# board.net
KiCad netlist of a schematic drawn in EAGLE
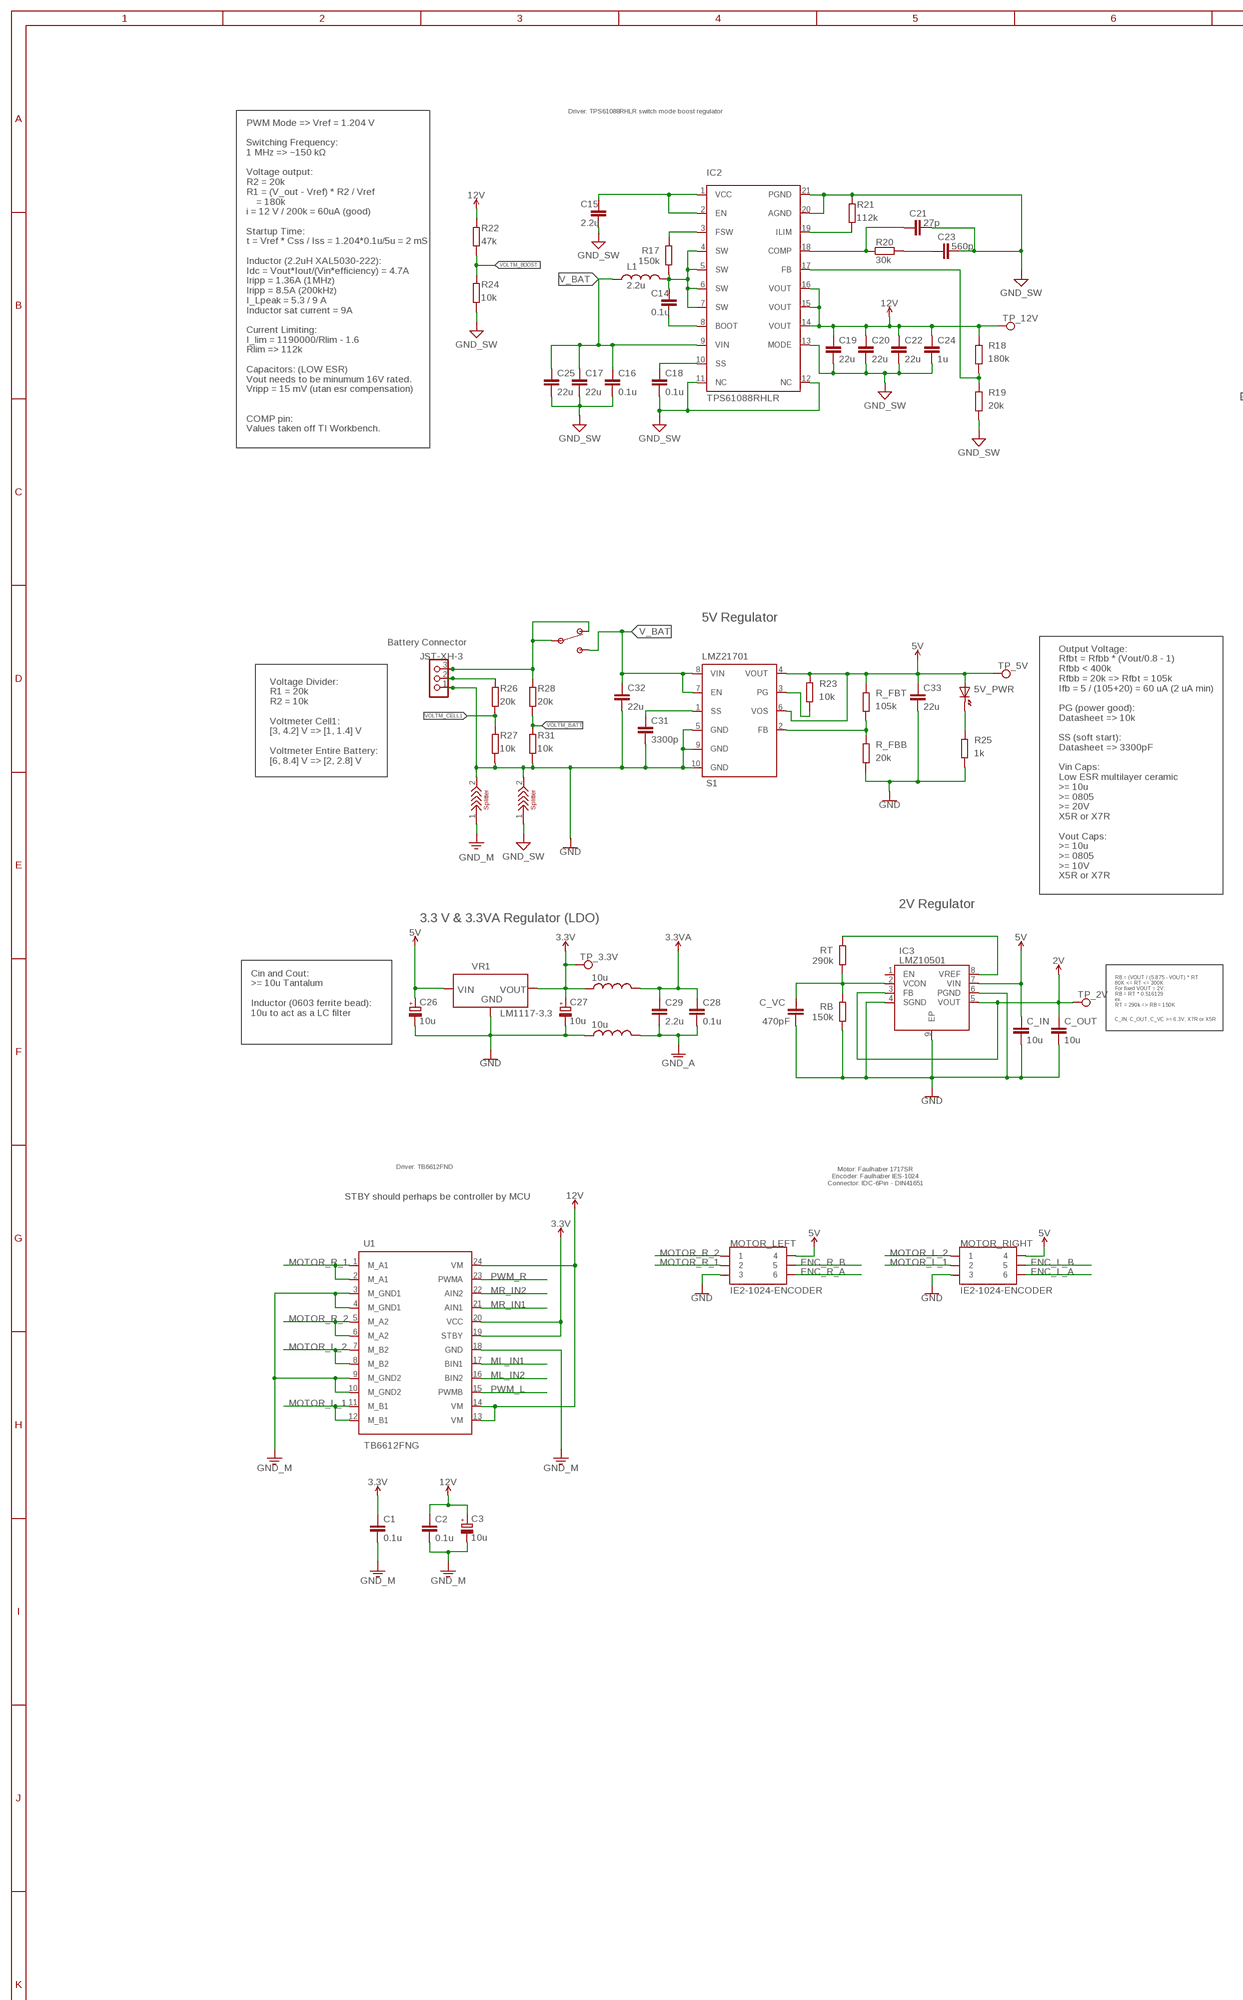
[diagram p0: schematic, sheet 1, part 1 of 3]
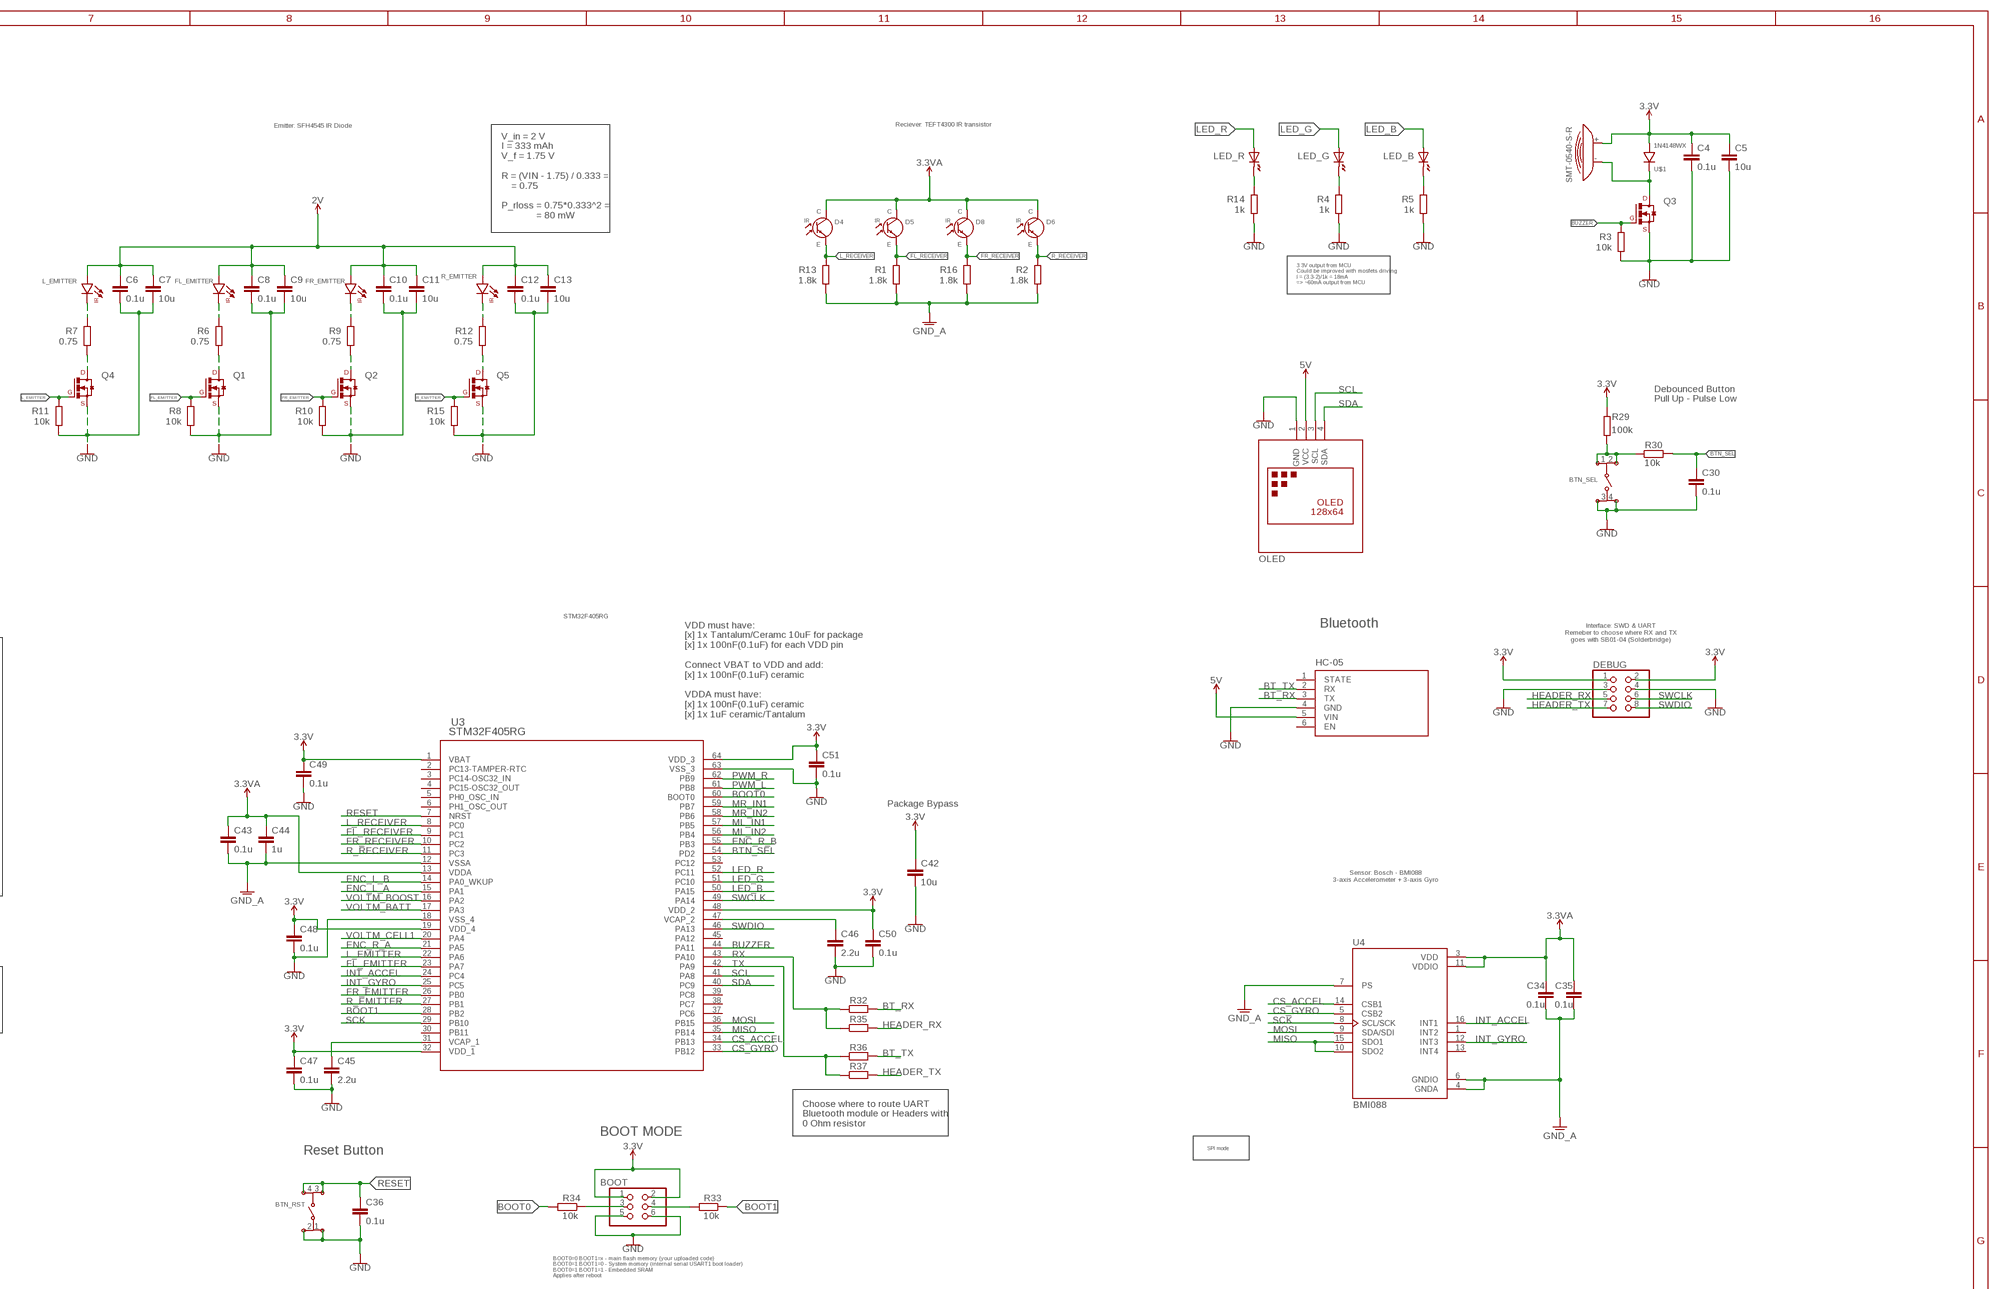
[diagram p1: schematic, sheet 1, part 2 of 3]
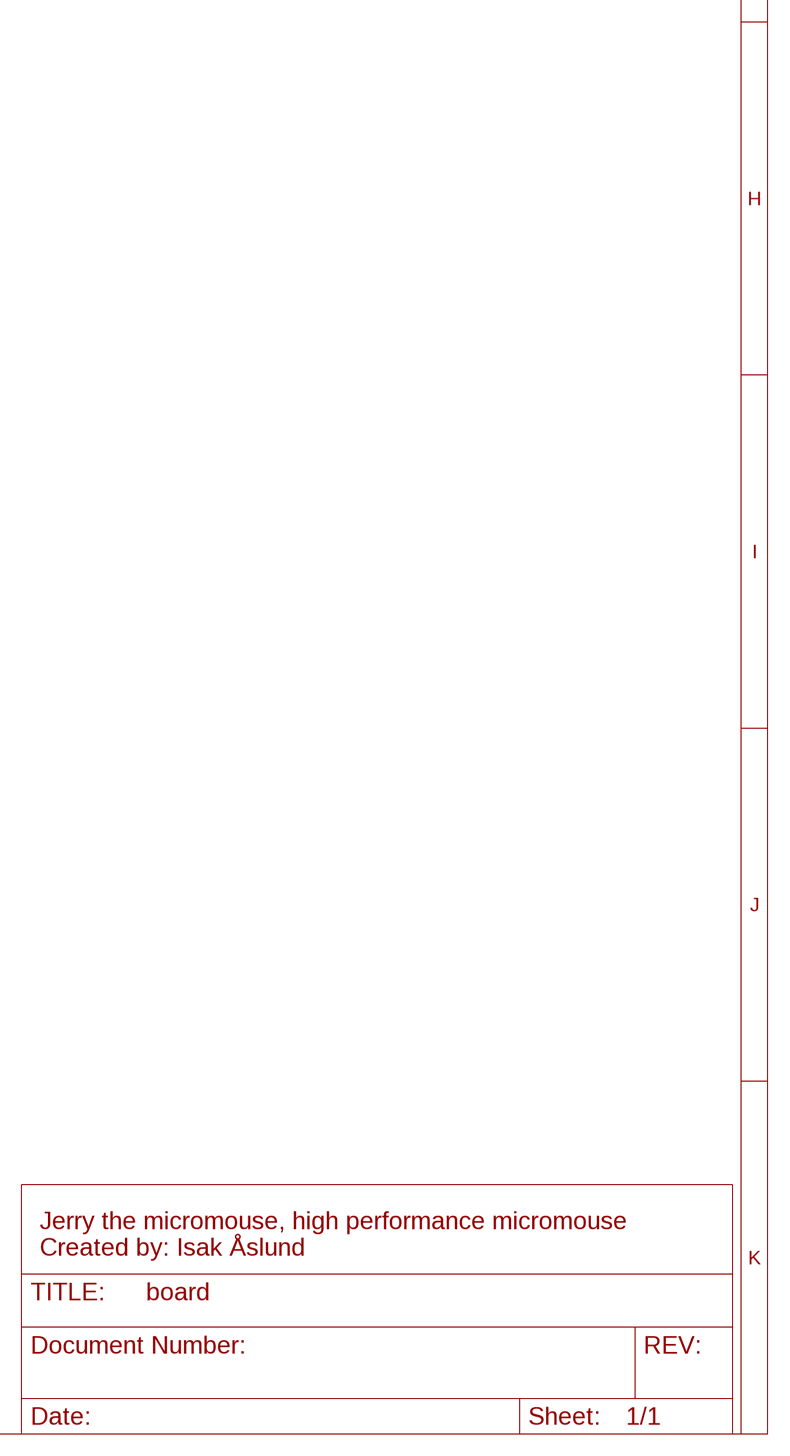
[diagram p2: schematic, sheet 1, part 3 of 3]

(export (version "E")
  (design (tool "Eeschema 10.0.6"))
  (components
    (comp (ref "5V_PWR")
      (value "CHIP-LED0603")
      (footprint "eagle-import:CHIP-LED0603")
      (libsource (lib "eagle-import") (part "CHIP-LED0603"))
    )
    (comp (ref "BOOT")
      (value "PINHD-2X3")
      (footprint "eagle-import:2X03")
      (libsource (lib "eagle-import") (part "PINHD-2X3"))
    )
    (comp (ref "BTN_RST")
      (value "KMR621NGLFS")
      (footprint "eagle-import:KMR621NGLFS")
      (libsource (lib "eagle-import") (part "KMR621NGLFS"))
    )
    (comp (ref "BTN_SEL")
      (value "KMR621NGLFS")
      (footprint "eagle-import:KMR621NGLFS")
      (libsource (lib "eagle-import") (part "KMR621NGLFS"))
    )
    (comp (ref "C1")
      (value "0.1u")
      (footprint "eagle-import:C0603")
      (libsource (lib "eagle-import") (part "C0603"))
    )
    (comp (ref "C2")
      (value "0.1u")
      (footprint "eagle-import:C0603")
      (libsource (lib "eagle-import") (part "C0603"))
    )
    (comp (ref "C3")
      (value "10u")
      (footprint "eagle-import:EIA_6032-28")
      (libsource (lib "eagle-import") (part "KEMET_C"))
    )
    (comp (ref "C4")
      (value "0.1u")
      (footprint "eagle-import:C0603")
      (libsource (lib "eagle-import") (part "C0603"))
    )
    (comp (ref "C5")
      (value "10u")
      (footprint "eagle-import:C0603")
      (libsource (lib "eagle-import") (part "C0603"))
    )
    (comp (ref "C6")
      (value "0.1u")
      (footprint "eagle-import:C0603")
      (libsource (lib "eagle-import") (part "C0603"))
    )
    (comp (ref "C7")
      (value "10u")
      (footprint "eagle-import:C0603")
      (libsource (lib "eagle-import") (part "C0603"))
    )
    (comp (ref "C8")
      (value "0.1u")
      (footprint "eagle-import:C0603")
      (libsource (lib "eagle-import") (part "C0603"))
    )
    (comp (ref "C9")
      (value "10u")
      (footprint "eagle-import:C0603")
      (libsource (lib "eagle-import") (part "C0603"))
    )
    (comp (ref "C10")
      (value "0.1u")
      (footprint "eagle-import:C0603")
      (libsource (lib "eagle-import") (part "C0603"))
    )
    (comp (ref "C11")
      (value "10u")
      (footprint "eagle-import:C0603")
      (libsource (lib "eagle-import") (part "C0603"))
    )
    (comp (ref "C12")
      (value "0.1u")
      (footprint "eagle-import:C0603")
      (libsource (lib "eagle-import") (part "C0603"))
    )
    (comp (ref "C13")
      (value "10u")
      (footprint "eagle-import:C0603")
      (libsource (lib "eagle-import") (part "C0603"))
    )
    (comp (ref "C14")
      (value "0.1u")
      (footprint "eagle-import:C0603")
      (libsource (lib "eagle-import") (part "C0603"))
    )
    (comp (ref "C15")
      (value "2.2u")
      (footprint "eagle-import:C0603")
      (libsource (lib "eagle-import") (part "C0603"))
    )
    (comp (ref "C16")
      (value "0.1u")
      (footprint "eagle-import:C0805")
      (libsource (lib "eagle-import") (part "C0805"))
    )
    (comp (ref "C17")
      (value "22u")
      (footprint "eagle-import:C0805")
      (libsource (lib "eagle-import") (part "C0805"))
    )
    (comp (ref "C18")
      (value "0.1u")
      (footprint "eagle-import:C0603")
      (libsource (lib "eagle-import") (part "C0603"))
    )
    (comp (ref "C19")
      (value "22u")
      (footprint "eagle-import:C0805")
      (libsource (lib "eagle-import") (part "C0805"))
    )
    (comp (ref "C20")
      (value "22u")
      (footprint "eagle-import:C0805")
      (libsource (lib "eagle-import") (part "C0805"))
    )
    (comp (ref "C21")
      (value "27p")
      (footprint "eagle-import:C0603")
      (libsource (lib "eagle-import") (part "C0603"))
    )
    (comp (ref "C22")
      (value "22u")
      (footprint "eagle-import:C0805")
      (libsource (lib "eagle-import") (part "C0805"))
    )
    (comp (ref "C23")
      (value "560p")
      (footprint "eagle-import:C0603")
      (libsource (lib "eagle-import") (part "C0603"))
    )
    (comp (ref "C24")
      (value "1u")
      (footprint "eagle-import:C0805")
      (libsource (lib "eagle-import") (part "C0805"))
    )
    (comp (ref "C25")
      (value "22u")
      (footprint "eagle-import:C0805")
      (libsource (lib "eagle-import") (part "C0805"))
    )
    (comp (ref "C26")
      (value "10u")
      (footprint "eagle-import:SMC_A")
      (libsource (lib "eagle-import") (part "SMC_A"))
    )
    (comp (ref "C27")
      (value "10u")
      (footprint "eagle-import:SMC_A")
      (libsource (lib "eagle-import") (part "SMC_A"))
    )
    (comp (ref "C28")
      (value "0.1u")
      (footprint "eagle-import:C0603")
      (libsource (lib "eagle-import") (part "C0603"))
    )
    (comp (ref "C29")
      (value "2.2u")
      (footprint "eagle-import:C0603")
      (libsource (lib "eagle-import") (part "C0603"))
    )
    (comp (ref "C30")
      (value "0.1u")
      (footprint "eagle-import:C0603")
      (libsource (lib "eagle-import") (part "C0603"))
    )
    (comp (ref "C31")
      (value "3300p")
      (footprint "eagle-import:C0603")
      (libsource (lib "eagle-import") (part "C0603"))
    )
    (comp (ref "C32")
      (value "22u")
      (footprint "eagle-import:C0805")
      (libsource (lib "eagle-import") (part "C0805"))
    )
    (comp (ref "C33")
      (value "22u")
      (footprint "eagle-import:C0805")
      (libsource (lib "eagle-import") (part "C0805"))
    )
    (comp (ref "C34")
      (value "0.1u")
      (footprint "eagle-import:C0603")
      (libsource (lib "eagle-import") (part "C0603"))
    )
    (comp (ref "C35")
      (value "0.1u")
      (footprint "eagle-import:C0603")
      (libsource (lib "eagle-import") (part "C0603"))
    )
    (comp (ref "C36")
      (value "0.1u")
      (footprint "eagle-import:C0603")
      (libsource (lib "eagle-import") (part "C0603"))
    )
    (comp (ref "C42")
      (value "10u")
      (footprint "eagle-import:C0603")
      (libsource (lib "eagle-import") (part "C0603"))
    )
    (comp (ref "C43")
      (value "0.1u")
      (footprint "eagle-import:C0603")
      (libsource (lib "eagle-import") (part "C0603"))
    )
    (comp (ref "C44")
      (value "1u")
      (footprint "eagle-import:C0603")
      (libsource (lib "eagle-import") (part "C0603"))
    )
    (comp (ref "C45")
      (value "2.2u")
      (footprint "eagle-import:C0603")
      (libsource (lib "eagle-import") (part "C0603"))
    )
    (comp (ref "C46")
      (value "2.2u")
      (footprint "eagle-import:C0603")
      (libsource (lib "eagle-import") (part "C0603"))
    )
    (comp (ref "C47")
      (value "0.1u")
      (footprint "eagle-import:C0603")
      (libsource (lib "eagle-import") (part "C0603"))
    )
    (comp (ref "C48")
      (value "0.1u")
      (footprint "eagle-import:C0603")
      (libsource (lib "eagle-import") (part "C0603"))
    )
    (comp (ref "C49")
      (value "0.1u")
      (footprint "eagle-import:C0603")
      (libsource (lib "eagle-import") (part "C0603"))
    )
    (comp (ref "C50")
      (value "0.1u")
      (footprint "eagle-import:C0603")
      (libsource (lib "eagle-import") (part "C0603"))
    )
    (comp (ref "C51")
      (value "0.1u")
      (footprint "eagle-import:C0603")
      (libsource (lib "eagle-import") (part "C0603"))
    )
    (comp (ref "C_IN")
      (value "10u")
      (footprint "eagle-import:C0805")
      (libsource (lib "eagle-import") (part "C0805"))
    )
    (comp (ref "C_OUT")
      (value "10u")
      (footprint "eagle-import:C0805")
      (libsource (lib "eagle-import") (part "C0805"))
    )
    (comp (ref "C_VC")
      (value "470pF")
      (footprint "eagle-import:C0603")
      (libsource (lib "eagle-import") (part "C0603"))
    )
    (comp (ref "D4")
      (value "TEFT4300")
      (footprint "eagle-import:3MM_PHOTOTRANSISTOR")
      (libsource (lib "eagle-import") (part "TEFT4300"))
    )
    (comp (ref "D5")
      (value "TEFT4300")
      (footprint "eagle-import:3MM_PHOTOTRANSISTOR")
      (libsource (lib "eagle-import") (part "TEFT4300"))
    )
    (comp (ref "D6")
      (value "TEFT4300")
      (footprint "eagle-import:3MM_PHOTOTRANSISTOR")
      (libsource (lib "eagle-import") (part "TEFT4300"))
    )
    (comp (ref "D8")
      (value "TEFT4300")
      (footprint "eagle-import:3MM_PHOTOTRANSISTOR")
      (libsource (lib "eagle-import") (part "TEFT4300"))
    )
    (comp (ref "DEBUG")
      (value "PINHD-2X4")
      (footprint "eagle-import:2X04")
      (libsource (lib "eagle-import") (part "PINHD-2X4"))
    )
    (comp (ref "FL_EMITTER")
      (value "SFH_4545")
      (footprint "eagle-import:SFH_4545")
      (libsource (lib "eagle-import") (part "SFH_4545"))
    )
    (comp (ref "FP1")
      (value "10u")
      (footprint "eagle-import:R0805")
      (libsource (lib "eagle-import") (part "WE-CBF_0805"))
    )
    (comp (ref "FP2")
      (value "10u")
      (footprint "eagle-import:R0805")
      (libsource (lib "eagle-import") (part "WE-CBF_0805"))
    )
    (comp (ref "FR_EMITTER")
      (value "SFH_4545")
      (footprint "eagle-import:SFH_4545")
      (libsource (lib "eagle-import") (part "SFH_4545"))
    )
    (comp (ref "HC-05")
      (value "WIRELESS-BLUETOOTH-HC-05")
      (footprint "eagle-import:WIRELESS-BLUETOOTH-HC-05")
      (libsource (lib "eagle-import") (part "WIRELESS-BLUETOOTH-HC-05"))
    )
    (comp (ref "IC2")
      (value "TPS61088RHLR")
      (footprint "eagle-import:RHL(R-PVQFN-N20)_1")
      (fields (field (name "MOUSER_PART_NUMBER") "595-TPS61088RHLR"))
      (libsource (lib "eagle-import") (part "TPS61088RHLR"))
    )
    (comp (ref "IC3")
      (value "LMZ10501")
      (footprint "eagle-import:SON65P260X300X150-9N")
      (fields
        (field (name "MANUFACTURER_PART_NUMBER") "LMZ10501SILT")
        (field (name "MOUSER_PART_NUMBER") "595-LMZ10501SILT")
      )
      (libsource (lib "eagle-import") (part "LMZ10501"))
    )
    (comp (ref "L1")
      (value "2.2u")
      (footprint "eagle-import:XAL5030")
      (fields
        (field (name "MANUFACTURER_PART_NUMBER") "XAL5030-222MEC")
        (field (name "MOUSER_PART_NUMBER") "994-XAL5030-222MEC")
      )
      (libsource (lib "eagle-import") (part "XAL5030-222MEC"))
    )
    (comp (ref "LED_B")
      (value "CHIP-LED0603")
      (footprint "eagle-import:CHIP-LED0603")
      (libsource (lib "eagle-import") (part "CHIP-LED0603"))
    )
    (comp (ref "LED_G")
      (value "CHIP-LED0603")
      (footprint "eagle-import:CHIP-LED0603")
      (libsource (lib "eagle-import") (part "CHIP-LED0603"))
    )
    (comp (ref "LED_R")
      (value "CHIP-LED0603")
      (footprint "eagle-import:CHIP-LED0603")
      (libsource (lib "eagle-import") (part "CHIP-LED0603"))
    )
    (comp (ref "L_EMITTER")
      (value "SFH_4545")
      (footprint "eagle-import:SFH_4545")
      (libsource (lib "eagle-import") (part "SFH_4545"))
    )
    (comp (ref "MOTOR_LEFT")
      (value "IE2-1024-ENCODER")
      (footprint "eagle-import:IE2-1024-ENCODER")
      (libsource (lib "eagle-import") (part "IE2-1024-ENCODER"))
    )
    (comp (ref "MOTOR_RIGHT")
      (value "IE2-1024-ENCODER")
      (footprint "eagle-import:IE2-1024-ENCODER")
      (libsource (lib "eagle-import") (part "IE2-1024-ENCODER"))
    )
    (comp (ref "OLED")
      (value "DISPLAY-OLED-128X64-I2C")
      (footprint "eagle-import:DISPLAY-OLED-128X64-I2C")
      (libsource (lib "eagle-import") (part "DISPLAY-OLED-128X64-I2C"))
    )
    (comp (ref "Q1")
      (value "IRFML8244TRPBF")
      (footprint "eagle-import:SOT95P235X110-3")
      (libsource (lib "eagle-import") (part "IRFML8244TRPBF"))
    )
    (comp (ref "Q2")
      (value "IRFML8244TRPBF")
      (footprint "eagle-import:SOT95P235X110-3")
      (libsource (lib "eagle-import") (part "IRFML8244TRPBF"))
    )
    (comp (ref "Q3")
      (value "IRFML8244TRPBF")
      (footprint "eagle-import:SOT95P235X110-3")
      (libsource (lib "eagle-import") (part "IRFML8244TRPBF"))
    )
    (comp (ref "Q4")
      (value "IRFML8244TRPBF")
      (footprint "eagle-import:SOT95P235X110-3")
      (libsource (lib "eagle-import") (part "IRFML8244TRPBF"))
    )
    (comp (ref "Q5")
      (value "IRFML8244TRPBF")
      (footprint "eagle-import:SOT95P235X110-3")
      (libsource (lib "eagle-import") (part "IRFML8244TRPBF"))
    )
    (comp (ref "R1")
      (value "1.8k")
      (footprint "eagle-import:R0603")
      (libsource (lib "eagle-import") (part "R0603"))
    )
    (comp (ref "R2")
      (value "1.8k")
      (footprint "eagle-import:R0603")
      (libsource (lib "eagle-import") (part "R0603"))
    )
    (comp (ref "R3")
      (value "10k")
      (footprint "eagle-import:R0603")
      (libsource (lib "eagle-import") (part "R0603"))
    )
    (comp (ref "R4")
      (value "1k")
      (footprint "eagle-import:R0603")
      (libsource (lib "eagle-import") (part "R0603"))
    )
    (comp (ref "R5")
      (value "1k")
      (footprint "eagle-import:R0603")
      (libsource (lib "eagle-import") (part "R0603"))
    )
    (comp (ref "R6")
      (value "0.75")
      (footprint "eagle-import:R0603")
      (libsource (lib "eagle-import") (part "R0603"))
    )
    (comp (ref "R7")
      (value "0.75")
      (footprint "eagle-import:R0603")
      (libsource (lib "eagle-import") (part "R0603"))
    )
    (comp (ref "R8")
      (value "10k")
      (footprint "eagle-import:R0603")
      (libsource (lib "eagle-import") (part "R0603"))
    )
    (comp (ref "R9")
      (value "0.75")
      (footprint "eagle-import:R0603")
      (libsource (lib "eagle-import") (part "R0603"))
    )
    (comp (ref "R10")
      (value "10k")
      (footprint "eagle-import:R0603")
      (libsource (lib "eagle-import") (part "R0603"))
    )
    (comp (ref "R11")
      (value "10k")
      (footprint "eagle-import:R0603")
      (libsource (lib "eagle-import") (part "R0603"))
    )
    (comp (ref "R12")
      (value "0.75")
      (footprint "eagle-import:R0603")
      (libsource (lib "eagle-import") (part "R0603"))
    )
    (comp (ref "R13")
      (value "1.8k")
      (footprint "eagle-import:R0603")
      (libsource (lib "eagle-import") (part "R0603"))
    )
    (comp (ref "R14")
      (value "1k")
      (footprint "eagle-import:R0603")
      (libsource (lib "eagle-import") (part "R0603"))
    )
    (comp (ref "R15")
      (value "10k")
      (footprint "eagle-import:R0603")
      (libsource (lib "eagle-import") (part "R0603"))
    )
    (comp (ref "R16")
      (value "1.8k")
      (footprint "eagle-import:R0603")
      (libsource (lib "eagle-import") (part "R0603"))
    )
    (comp (ref "R17")
      (value "150k")
      (footprint "eagle-import:R0603")
      (libsource (lib "eagle-import") (part "R0603"))
    )
    (comp (ref "R18")
      (value "180k")
      (footprint "eagle-import:R0603")
      (libsource (lib "eagle-import") (part "R0603"))
    )
    (comp (ref "R19")
      (value "20k")
      (footprint "eagle-import:R0603")
      (libsource (lib "eagle-import") (part "R0603"))
    )
    (comp (ref "R20")
      (value "30k")
      (footprint "eagle-import:R0603")
      (libsource (lib "eagle-import") (part "R0603"))
    )
    (comp (ref "R21")
      (value "112k")
      (footprint "eagle-import:R0603")
      (libsource (lib "eagle-import") (part "R0603"))
    )
    (comp (ref "R22")
      (value "47k")
      (footprint "eagle-import:R0603")
      (libsource (lib "eagle-import") (part "R0603"))
    )
    (comp (ref "R23")
      (value "10k")
      (footprint "eagle-import:R0603")
      (fields (field (name "TOLERANCE") "1%"))
      (libsource (lib "eagle-import") (part "R0603"))
    )
    (comp (ref "R24")
      (value "10k")
      (footprint "eagle-import:R0603")
      (libsource (lib "eagle-import") (part "R0603"))
    )
    (comp (ref "R25")
      (value "1k")
      (footprint "eagle-import:R0603")
      (libsource (lib "eagle-import") (part "R0603"))
    )
    (comp (ref "R26")
      (value "20k")
      (footprint "eagle-import:R0603")
      (libsource (lib "eagle-import") (part "R0603"))
    )
    (comp (ref "R27")
      (value "10k")
      (footprint "eagle-import:R0603")
      (libsource (lib "eagle-import") (part "R0603"))
    )
    (comp (ref "R28")
      (value "20k")
      (footprint "eagle-import:R0603")
      (libsource (lib "eagle-import") (part "R0603"))
    )
    (comp (ref "R29")
      (value "100k")
      (footprint "eagle-import:R0603")
      (libsource (lib "eagle-import") (part "R0603"))
    )
    (comp (ref "R30")
      (value "10k")
      (footprint "eagle-import:R0603")
      (libsource (lib "eagle-import") (part "R0603"))
    )
    (comp (ref "R31")
      (value "10k")
      (footprint "eagle-import:R0603")
      (libsource (lib "eagle-import") (part "R0603"))
    )
    (comp (ref "R32")
      (value "0")
      (footprint "eagle-import:R0603")
      (libsource (lib "eagle-import") (part "R0603"))
    )
    (comp (ref "R33")
      (value "10k")
      (footprint "eagle-import:R0603")
      (libsource (lib "eagle-import") (part "R0603"))
    )
    (comp (ref "R34")
      (value "10k")
      (footprint "eagle-import:R0603")
      (libsource (lib "eagle-import") (part "R0603"))
    )
    (comp (ref "R35")
      (value "0")
      (footprint "eagle-import:R0603")
      (libsource (lib "eagle-import") (part "R0603"))
    )
    (comp (ref "R36")
      (value "0")
      (footprint "eagle-import:R0603")
      (libsource (lib "eagle-import") (part "R0603"))
    )
    (comp (ref "R37")
      (value "0")
      (footprint "eagle-import:R0603")
      (libsource (lib "eagle-import") (part "R0603"))
    )
    (comp (ref "RB")
      (value "150k")
      (footprint "eagle-import:R0603")
      (libsource (lib "eagle-import") (part "R0603"))
    )
    (comp (ref "RT")
      (value "290k")
      (footprint "eagle-import:R0603")
      (fields (field (name "TOLERANCE") "1%"))
      (libsource (lib "eagle-import") (part "R0603"))
    )
    (comp (ref "R_EMITTER")
      (value "SFH_4545")
      (footprint "eagle-import:SFH_4545")
      (libsource (lib "eagle-import") (part "SFH_4545"))
    )
    (comp (ref "R_FBB")
      (value "20k")
      (footprint "eagle-import:R0603")
      (libsource (lib "eagle-import") (part "R0603"))
    )
    (comp (ref "R_FBT")
      (value "105k")
      (footprint "eagle-import:R0603")
      (libsource (lib "eagle-import") (part "R0603"))
    )
    (comp (ref "S1")
      (value "LMZ21701")
      (footprint "eagle-import:LMZ21701")
      (fields
        (field (name "MANUFACTURER_PART_NUMBER") "LMZ21701SILR")
        (field (name "MOUSER_PART_NUMBER") "595-LMZ21701SILR")
      )
      (libsource (lib "eagle-import") (part "LMZ21701"))
    )
    (comp (ref "SW")
      (value "SPDT-500SSP1S1M6QEA")
      (footprint "eagle-import:500SSP1S1M6QEA")
      (libsource (lib "eagle-import") (part "SPDT-500SSP1S1M6QEA"))
    )
    (comp (ref "TP_2V")
      (value "TEST-POINT3X5")
      (footprint "eagle-import:PAD.03X.05")
      (libsource (lib "eagle-import") (part "TEST-POINT3X5"))
    )
    (comp (ref "TP_3.3V")
      (value "TEST-POINT3X5")
      (footprint "eagle-import:PAD.03X.05")
      (libsource (lib "eagle-import") (part "TEST-POINT3X5"))
    )
    (comp (ref "TP_5V")
      (value "TEST-POINT3X5")
      (footprint "eagle-import:PAD.03X.05")
      (libsource (lib "eagle-import") (part "TEST-POINT3X5"))
    )
    (comp (ref "TP_12V")
      (value "TEST-POINT3X5")
      (footprint "eagle-import:PAD.03X.05")
      (libsource (lib "eagle-import") (part "TEST-POINT3X5"))
    )
    (comp (ref "U$1")
      (value "1N4148WX")
      (footprint "eagle-import:1N4148WX_SOD-323-2")
      (libsource (lib "eagle-import") (part "DIODE_1N4148WX"))
    )
    (comp (ref "U$4")
      (value "SMT-0540-S-R")
      (footprint "eagle-import:SMT-0540-S-R")
      (libsource (lib "eagle-import") (part "SMT-0540-S-R"))
    )
    (comp (ref "U$6")
      (value "SPLITTER")
      (footprint "eagle-import:SPLITTER")
      (libsource (lib "eagle-import") (part "SPLITTER"))
    )
    (comp (ref "U$7")
      (value "SPLITTER")
      (footprint "eagle-import:SPLITTER")
      (libsource (lib "eagle-import") (part "SPLITTER"))
    )
    (comp (ref "U$10")
      (value "JST-XH-3")
      (footprint "eagle-import:JST-XH-03")
      (libsource (lib "eagle-import") (part "JST-XH-3"))
    )
    (comp (ref "U1")
      (value "TB6612FNG")
      (footprint "eagle-import:SOP65P760X160-24")
      (libsource (lib "eagle-import") (part "TB6612FNG"))
    )
    (comp (ref "U3")
      (value "STM32F405RG")
      (footprint "eagle-import:LQFP-64")
      (libsource (lib "eagle-import") (part "STM32F405RG"))
    )
    (comp (ref "U4")
      (value "BMI088")
      (footprint "eagle-import:PQFN50P450X300X100-16N")
      (fields (field (name "MF") "Bosch Sensortec"))
      (libsource (lib "eagle-import") (part "BMI088"))
    )
    (comp (ref "VR1")
      (value "LM1117-3.3")
      (footprint "eagle-import:SOT230P700X180-4")
      (libsource (lib "eagle-import") (part "LM1117-3.3"))
    )
  )
  (nets
    (net (code "1") (name "/BT_RX") (class "Default")
      (node (ref "HC-05") (pin "3") (pinfunction "TX_3") (pintype "output"))
      (node (ref "R32") (pin "2") (pinfunction "2_2") (pintype "passive"))
    )
    (net (code "2") (name "/BT_TX") (class "Default")
      (node (ref "HC-05") (pin "2") (pinfunction "RX_2") (pintype "input"))
      (node (ref "R36") (pin "2") (pinfunction "2_2") (pintype "passive"))
    )
    (net (code "3") (name "/CS_ACCEL") (class "Default")
      (node (ref "U3") (pin "34") (pinfunction "PB13_34") (pintype "bidirectional"))
      (node (ref "U4") (pin "14") (pinfunction "CSB1_14") (pintype "input"))
    )
    (net (code "4") (name "/CS_GYRO") (class "Default")
      (node (ref "U3") (pin "33") (pinfunction "PB12_33") (pintype "bidirectional"))
      (node (ref "U4") (pin "5") (pinfunction "CSB2_5") (pintype "input"))
    )
    (net (code "5") (name "/ENC_L_A") (class "Default")
      (node (ref "MOTOR_RIGHT") (pin "6") (pinfunction "6_6") (pintype "bidirectional"))
      (node (ref "U3") (pin "15") (pinfunction "PA1_15") (pintype "bidirectional"))
    )
    (net (code "6") (name "/ENC_L_B") (class "Default")
      (node (ref "MOTOR_RIGHT") (pin "5") (pinfunction "5_5") (pintype "bidirectional"))
      (node (ref "U3") (pin "14") (pinfunction "PA0_WKUP_14") (pintype "bidirectional"))
    )
    (net (code "7") (name "/ENC_R_A") (class "Default")
      (node (ref "MOTOR_LEFT") (pin "6") (pinfunction "6_6") (pintype "bidirectional"))
      (node (ref "U3") (pin "21") (pinfunction "PA5_21") (pintype "bidirectional"))
    )
    (net (code "8") (name "/ENC_R_B") (class "Default")
      (node (ref "MOTOR_LEFT") (pin "5") (pinfunction "5_5") (pintype "bidirectional"))
      (node (ref "U3") (pin "55") (pinfunction "PB3_55") (pintype "bidirectional"))
    )
    (net (code "9") (name "/HEADER_RX") (class "Default")
      (node (ref "DEBUG") (pin "5") (pinfunction "5_5") (pintype "passive"))
      (node (ref "R35") (pin "2") (pinfunction "2_2") (pintype "passive"))
    )
    (net (code "10") (name "/HEADER_TX") (class "Default")
      (node (ref "DEBUG") (pin "7") (pinfunction "7_7") (pintype "passive"))
      (node (ref "R37") (pin "2") (pinfunction "2_2") (pintype "passive"))
    )
    (net (code "11") (name "/INT_ACCEL") (class "Default")
      (node (ref "U3") (pin "24") (pinfunction "PC4_24") (pintype "bidirectional"))
      (node (ref "U4") (pin "16") (pinfunction "INT1_16") (pintype "bidirectional"))
    )
    (net (code "12") (name "/INT_GYRO") (class "Default")
      (node (ref "U3") (pin "25") (pinfunction "PC5_25") (pintype "bidirectional"))
      (node (ref "U4") (pin "12") (pinfunction "INT3_12") (pintype "bidirectional"))
    )
    (net (code "13") (name "/MISO") (class "Default")
      (node (ref "U3") (pin "35") (pinfunction "PB14_35") (pintype "bidirectional"))
      (node (ref "U4") (pin "10") (pinfunction "SDO2_10") (pintype "output"))
      (node (ref "U4") (pin "15") (pinfunction "SDO1_15") (pintype "output"))
    )
    (net (code "14") (name "/ML_IN1") (class "Default")
      (node (ref "U1") (pin "17") (pinfunction "BIN1_17") (pintype "input"))
      (node (ref "U3") (pin "57") (pinfunction "PB5_57") (pintype "bidirectional"))
    )
    (net (code "15") (name "/ML_IN2") (class "Default")
      (node (ref "U1") (pin "16") (pinfunction "BIN2_16") (pintype "input"))
      (node (ref "U3") (pin "56") (pinfunction "PB4_56") (pintype "bidirectional"))
    )
    (net (code "16") (name "/MOSI") (class "Default")
      (node (ref "U3") (pin "36") (pinfunction "PB15_36") (pintype "bidirectional"))
      (node (ref "U4") (pin "9") (pinfunction "SDA/SDI_9") (pintype "bidirectional"))
    )
    (net (code "17") (name "/MOTOR_L_1") (class "Default")
      (node (ref "MOTOR_RIGHT") (pin "2") (pinfunction "2_2") (pintype "bidirectional"))
      (node (ref "U1") (pin "11") (pinfunction "M_B1_11") (pintype "bidirectional"))
      (node (ref "U1") (pin "12") (pinfunction "M_B1_12") (pintype "bidirectional"))
    )
    (net (code "18") (name "/MOTOR_L_2") (class "Default")
      (node (ref "MOTOR_RIGHT") (pin "1") (pinfunction "1_1") (pintype "bidirectional"))
      (node (ref "U1") (pin "7") (pinfunction "M_B2_7") (pintype "bidirectional"))
      (node (ref "U1") (pin "8") (pinfunction "M_B2_8") (pintype "bidirectional"))
    )
    (net (code "19") (name "/MOTOR_R_1") (class "Default")
      (node (ref "MOTOR_LEFT") (pin "2") (pinfunction "2_2") (pintype "bidirectional"))
      (node (ref "U1") (pin "1") (pinfunction "M_A1_1") (pintype "bidirectional"))
      (node (ref "U1") (pin "2") (pinfunction "M_A1_2") (pintype "bidirectional"))
    )
    (net (code "20") (name "/MOTOR_R_2") (class "Default")
      (node (ref "MOTOR_LEFT") (pin "1") (pinfunction "1_1") (pintype "bidirectional"))
      (node (ref "U1") (pin "5") (pinfunction "M_A2_5") (pintype "bidirectional"))
      (node (ref "U1") (pin "6") (pinfunction "M_A2_6") (pintype "bidirectional"))
    )
    (net (code "21") (name "/MR_IN1") (class "Default")
      (node (ref "U1") (pin "21") (pinfunction "AIN1_21") (pintype "input"))
      (node (ref "U3") (pin "59") (pinfunction "PB7_59") (pintype "bidirectional"))
    )
    (net (code "22") (name "/MR_IN2") (class "Default")
      (node (ref "U1") (pin "22") (pinfunction "AIN2_22") (pintype "input"))
      (node (ref "U3") (pin "58") (pinfunction "PB6_58") (pintype "bidirectional"))
    )
    (net (code "23") (name "/PWM_L") (class "Default")
      (node (ref "U1") (pin "15") (pinfunction "PWMB_15") (pintype "input"))
      (node (ref "U3") (pin "61") (pinfunction "PB8_61") (pintype "bidirectional"))
    )
    (net (code "24") (name "/PWM_R") (class "Default")
      (node (ref "U1") (pin "23") (pinfunction "PWMA_23") (pintype "input"))
      (node (ref "U3") (pin "62") (pinfunction "PB9_62") (pintype "bidirectional"))
    )
    (net (code "25") (name "/RX") (class "Default")
      (node (ref "R32") (pin "1") (pinfunction "1_1") (pintype "passive"))
      (node (ref "R35") (pin "1") (pinfunction "1_1") (pintype "passive"))
      (node (ref "U3") (pin "43") (pinfunction "PA10_43") (pintype "bidirectional"))
    )
    (net (code "26") (name "/SCK") (class "Default")
      (node (ref "U3") (pin "29") (pinfunction "PB10_29") (pintype "bidirectional"))
      (node (ref "U4") (pin "8") (pinfunction "SCL/SCK_8") (pintype "input"))
    )
    (net (code "27") (name "/SCL") (class "Default")
      (node (ref "OLED") (pin "3") (pinfunction "SCL_3") (pintype "bidirectional"))
      (node (ref "U3") (pin "41") (pinfunction "PA8_41") (pintype "bidirectional"))
    )
    (net (code "28") (name "/SDA") (class "Default")
      (node (ref "OLED") (pin "4") (pinfunction "SDA_4") (pintype "bidirectional"))
      (node (ref "U3") (pin "40") (pinfunction "PC9_40") (pintype "bidirectional"))
    )
    (net (code "29") (name "/SWCLK") (class "Default")
      (node (ref "DEBUG") (pin "6") (pinfunction "6_6") (pintype "passive"))
      (node (ref "U3") (pin "49") (pinfunction "PA14_49") (pintype "bidirectional"))
    )
    (net (code "30") (name "/SWDIO") (class "Default")
      (node (ref "DEBUG") (pin "8") (pinfunction "8_8") (pintype "passive"))
      (node (ref "U3") (pin "46") (pinfunction "PA13_46") (pintype "bidirectional"))
    )
    (net (code "31") (name "/TX") (class "Default")
      (node (ref "R36") (pin "1") (pinfunction "1_1") (pintype "passive"))
      (node (ref "R37") (pin "1") (pinfunction "1_1") (pintype "passive"))
      (node (ref "U3") (pin "42") (pinfunction "PA9_42") (pintype "bidirectional"))
    )
    (net (code "32") (name "2V") (class "Default")
      (node (ref "C10") (pin "1") (pinfunction "1_1") (pintype "passive"))
      (node (ref "C11") (pin "1") (pinfunction "1_1") (pintype "passive"))
      (node (ref "C12") (pin "1") (pinfunction "1_1") (pintype "passive"))
      (node (ref "C13") (pin "1") (pinfunction "1_1") (pintype "passive"))
      (node (ref "C6") (pin "1") (pinfunction "1_1") (pintype "passive"))
      (node (ref "C7") (pin "1") (pinfunction "1_1") (pintype "passive"))
      (node (ref "C8") (pin "1") (pinfunction "1_1") (pintype "passive"))
      (node (ref "C9") (pin "1") (pinfunction "1_1") (pintype "passive"))
      (node (ref "C_OUT") (pin "1") (pinfunction "1_1") (pintype "passive"))
      (node (ref "FL_EMITTER") (pin "+") (pinfunction "+_ANODE_+") (pintype "passive"))
      (node (ref "FR_EMITTER") (pin "+") (pinfunction "+_ANODE_+") (pintype "passive"))
      (node (ref "IC3") (pin "3") (pinfunction "FB_3") (pintype "input"))
      (node (ref "IC3") (pin "5") (pinfunction "VOUT_5") (pintype "power_in"))
      (node (ref "L_EMITTER") (pin "+") (pinfunction "+_ANODE_+") (pintype "passive"))
      (node (ref "R_EMITTER") (pin "+") (pinfunction "+_ANODE_+") (pintype "passive"))
      (node (ref "TP_2V") (pin "P$1") (pinfunction "1_P$1") (pintype "bidirectional"))
    )
    (net (code "33") (name "3.3V") (class "Default")
      (node (ref "BOOT") (pin "1") (pinfunction "1_1") (pintype "passive"))
      (node (ref "BOOT") (pin "2") (pinfunction "2_2") (pintype "passive"))
      (node (ref "C1") (pin "1") (pinfunction "1_1") (pintype "passive"))
      (node (ref "C27") (pin "+") (pinfunction "+_+") (pintype "passive"))
      (node (ref "C4") (pin "1") (pinfunction "1_1") (pintype "passive"))
      (node (ref "C42") (pin "1") (pinfunction "1_1") (pintype "passive"))
      (node (ref "C47") (pin "1") (pinfunction "1_1") (pintype "passive"))
      (node (ref "C48") (pin "1") (pinfunction "1_1") (pintype "passive"))
      (node (ref "C49") (pin "1") (pinfunction "1_1") (pintype "passive"))
      (node (ref "C5") (pin "1") (pinfunction "1_1") (pintype "passive"))
      (node (ref "C50") (pin "1") (pinfunction "1_1") (pintype "passive"))
      (node (ref "C51") (pin "1") (pinfunction "1_1") (pintype "passive"))
      (node (ref "DEBUG") (pin "1") (pinfunction "1_1") (pintype "passive"))
      (node (ref "DEBUG") (pin "2") (pinfunction "2_2") (pintype "passive"))
      (node (ref "FP1") (pin "1") (pinfunction "1_1") (pintype "passive"))
      (node (ref "R29") (pin "1") (pinfunction "1_1") (pintype "passive"))
      (node (ref "TP_3.3V") (pin "P$1") (pinfunction "1_P$1") (pintype "bidirectional"))
      (node (ref "U$1") (pin "+") (pinfunction "+_ANODE_+") (pintype "passive"))
      (node (ref "U$4") (pin "+") (pinfunction "+_+") (pintype "bidirectional"))
      (node (ref "U1") (pin "19") (pinfunction "STBY_19") (pintype "input"))
      (node (ref "U1") (pin "20") (pinfunction "VCC_20") (pintype "power_in"))
      (node (ref "U3") (pin "1") (pinfunction "VBAT_1") (pintype "power_in"))
      (node (ref "U3") (pin "19") (pinfunction "VDD_4_19") (pintype "power_in"))
      (node (ref "U3") (pin "32") (pinfunction "VDD_1_32") (pintype "power_in"))
      (node (ref "U3") (pin "48") (pinfunction "VDD_2_48") (pintype "power_in"))
      (node (ref "U3") (pin "64") (pinfunction "VDD_3_64") (pintype "power_in"))
      (node (ref "VR1") (pin "2") (pinfunction "VOUT_2") (pintype "power_in"))
      (node (ref "VR1") (pin "4") (pinfunction "VOUT_4") (pintype "power_in"))
    )
    (net (code "34") (name "3.3VA") (class "Default")
      (node (ref "C28") (pin "1") (pinfunction "1_1") (pintype "passive"))
      (node (ref "C29") (pin "1") (pinfunction "1_1") (pintype "passive"))
      (node (ref "C34") (pin "1") (pinfunction "1_1") (pintype "passive"))
      (node (ref "C35") (pin "1") (pinfunction "1_1") (pintype "passive"))
      (node (ref "C43") (pin "1") (pinfunction "1_1") (pintype "passive"))
      (node (ref "C44") (pin "1") (pinfunction "1_1") (pintype "passive"))
      (node (ref "D4") (pin "C") (pinfunction "C_+_C") (pintype "input"))
      (node (ref "D5") (pin "C") (pinfunction "C_+_C") (pintype "input"))
      (node (ref "D6") (pin "C") (pinfunction "C_+_C") (pintype "input"))
      (node (ref "D8") (pin "C") (pinfunction "C_+_C") (pintype "input"))
      (node (ref "FP1") (pin "2") (pinfunction "2_2") (pintype "passive"))
      (node (ref "U3") (pin "13") (pinfunction "VDDA_13") (pintype "power_in"))
      (node (ref "U4") (pin "11") (pinfunction "VDDIO_11") (pintype "power_in"))
      (node (ref "U4") (pin "3") (pinfunction "VDD_3") (pintype "power_in"))
    )
    (net (code "35") (name "5V") (class "Default")
      (node (ref "5V_PWR") (pin "A") (pinfunction "A_A") (pintype "passive"))
      (node (ref "C26") (pin "+") (pinfunction "+_+") (pintype "passive"))
      (node (ref "C33") (pin "1") (pinfunction "1_1") (pintype "passive"))
      (node (ref "C_IN") (pin "1") (pinfunction "1_1") (pintype "passive"))
      (node (ref "HC-05") (pin "5") (pinfunction "VIN_5") (pintype "power_in"))
      (node (ref "IC3") (pin "7") (pinfunction "VIN_7") (pintype "power_in"))
      (node (ref "MOTOR_LEFT") (pin "4") (pinfunction "4_4") (pintype "bidirectional"))
      (node (ref "MOTOR_RIGHT") (pin "4") (pinfunction "4_4") (pintype "bidirectional"))
      (node (ref "OLED") (pin "2") (pinfunction "VCC_2") (pintype "power_in"))
      (node (ref "R23") (pin "2") (pinfunction "2_2") (pintype "passive"))
      (node (ref "R_FBT") (pin "1") (pinfunction "1_1") (pintype "passive"))
      (node (ref "S1") (pin "4") (pinfunction "VOUT_4") (pintype "power_in"))
      (node (ref "S1") (pin "6") (pinfunction "VOS_6") (pintype "bidirectional"))
      (node (ref "TP_5V") (pin "P$1") (pinfunction "1_P$1") (pintype "bidirectional"))
      (node (ref "VR1") (pin "3") (pinfunction "VIN_3") (pintype "power_in"))
    )
    (net (code "36") (name "12V") (class "Default")
      (node (ref "C19") (pin "1") (pinfunction "1_1") (pintype "passive"))
      (node (ref "C2") (pin "1") (pinfunction "1_1") (pintype "passive"))
      (node (ref "C20") (pin "1") (pinfunction "1_1") (pintype "passive"))
      (node (ref "C22") (pin "1") (pinfunction "1_1") (pintype "passive"))
      (node (ref "C24") (pin "1") (pinfunction "1_1") (pintype "passive"))
      (node (ref "C3") (pin "1") (pinfunction "+_1") (pintype "passive"))
      (node (ref "IC2") (pin "14") (pinfunction "VOUT_14") (pintype "bidirectional"))
      (node (ref "IC2") (pin "15") (pinfunction "VOUT_15") (pintype "bidirectional"))
      (node (ref "IC2") (pin "16") (pinfunction "VOUT_16") (pintype "bidirectional"))
      (node (ref "R18") (pin "1") (pinfunction "1_1") (pintype "passive"))
      (node (ref "R22") (pin "2") (pinfunction "2_2") (pintype "passive"))
      (node (ref "TP_12V") (pin "P$1") (pinfunction "1_P$1") (pintype "bidirectional"))
      (node (ref "U1") (pin "13") (pinfunction "VM_13") (pintype "power_in"))
      (node (ref "U1") (pin "14") (pinfunction "VM_14") (pintype "power_in"))
      (node (ref "U1") (pin "24") (pinfunction "VM_24") (pintype "power_in"))
    )
    (net (code "37") (name "BOOT0") (class "Default")
      (node (ref "R34") (pin "2") (pinfunction "2_2") (pintype "passive"))
      (node (ref "U3") (pin "60") (pinfunction "BOOT0_60") (pintype "input"))
    )
    (net (code "38") (name "BOOT1") (class "Default")
      (node (ref "R33") (pin "1") (pinfunction "1_1") (pintype "passive"))
      (node (ref "U3") (pin "28") (pinfunction "PB2_28") (pintype "bidirectional"))
    )
    (net (code "39") (name "BTN_SEL") (class "Default")
      (node (ref "C30") (pin "1") (pinfunction "1_1") (pintype "passive"))
      (node (ref "R30") (pin "2") (pinfunction "2_2") (pintype "passive"))
      (node (ref "U3") (pin "54") (pinfunction "PD2_54") (pintype "bidirectional"))
    )
    (net (code "40") (name "BUZZER") (class "Default")
      (node (ref "Q3") (pin "1") (pinfunction "G_1") (pintype "passive"))
      (node (ref "R3") (pin "2") (pinfunction "2_2") (pintype "passive"))
      (node (ref "U3") (pin "44") (pinfunction "PA11_44") (pintype "bidirectional"))
    )
    (net (code "41") (name "FL_EMITTER") (class "Default")
      (node (ref "Q1") (pin "1") (pinfunction "G_1") (pintype "passive"))
      (node (ref "R8") (pin "2") (pinfunction "2_2") (pintype "passive"))
      (node (ref "U3") (pin "23") (pinfunction "PA7_23") (pintype "bidirectional"))
    )
    (net (code "42") (name "FL_RECEIVER") (class "Default")
      (node (ref "D5") (pin "E") (pinfunction "E_-_E") (pintype "output"))
      (node (ref "R1") (pin "2") (pinfunction "2_2") (pintype "passive"))
      (node (ref "U3") (pin "9") (pinfunction "PC1_9") (pintype "bidirectional"))
    )
    (net (code "43") (name "FR_EMITTER") (class "Default")
      (node (ref "Q2") (pin "1") (pinfunction "G_1") (pintype "passive"))
      (node (ref "R10") (pin "2") (pinfunction "2_2") (pintype "passive"))
      (node (ref "U3") (pin "26") (pinfunction "PB0_26") (pintype "bidirectional"))
    )
    (net (code "44") (name "FR_RECEIVER") (class "Default")
      (node (ref "D8") (pin "E") (pinfunction "E_-_E") (pintype "output"))
      (node (ref "R16") (pin "2") (pinfunction "2_2") (pintype "passive"))
      (node (ref "U3") (pin "10") (pinfunction "PC2_10") (pintype "bidirectional"))
    )
    (net (code "45") (name "GND") (class "Default")
      (node (ref "BOOT") (pin "5") (pinfunction "5_5") (pintype "passive"))
      (node (ref "BOOT") (pin "6") (pinfunction "6_6") (pintype "passive"))
      (node (ref "BTN_RST") (pin "1") (pinfunction "1_1") (pintype "bidirectional"))
      (node (ref "BTN_RST") (pin "2") (pinfunction "2_2") (pintype "bidirectional"))
      (node (ref "BTN_SEL") (pin "3") (pinfunction "3_3") (pintype "bidirectional"))
      (node (ref "BTN_SEL") (pin "4") (pinfunction "4_4") (pintype "bidirectional"))
      (node (ref "C10") (pin "2") (pinfunction "2_2") (pintype "passive"))
      (node (ref "C11") (pin "2") (pinfunction "2_2") (pintype "passive"))
      (node (ref "C12") (pin "2") (pinfunction "2_2") (pintype "passive"))
      (node (ref "C13") (pin "2") (pinfunction "2_2") (pintype "passive"))
      (node (ref "C26") (pin "-") (pinfunction "-_-") (pintype "passive"))
      (node (ref "C27") (pin "-") (pinfunction "-_-") (pintype "passive"))
      (node (ref "C30") (pin "2") (pinfunction "2_2") (pintype "passive"))
      (node (ref "C31") (pin "2") (pinfunction "2_2") (pintype "passive"))
      (node (ref "C32") (pin "2") (pinfunction "2_2") (pintype "passive"))
      (node (ref "C33") (pin "2") (pinfunction "2_2") (pintype "passive"))
      (node (ref "C36") (pin "2") (pinfunction "2_2") (pintype "passive"))
      (node (ref "C4") (pin "2") (pinfunction "2_2") (pintype "passive"))
      (node (ref "C42") (pin "2") (pinfunction "2_2") (pintype "passive"))
      (node (ref "C45") (pin "2") (pinfunction "2_2") (pintype "passive"))
      (node (ref "C46") (pin "2") (pinfunction "2_2") (pintype "passive"))
      (node (ref "C47") (pin "2") (pinfunction "2_2") (pintype "passive"))
      (node (ref "C48") (pin "2") (pinfunction "2_2") (pintype "passive"))
      (node (ref "C49") (pin "2") (pinfunction "2_2") (pintype "passive"))
      (node (ref "C5") (pin "2") (pinfunction "2_2") (pintype "passive"))
      (node (ref "C50") (pin "2") (pinfunction "2_2") (pintype "passive"))
      (node (ref "C51") (pin "2") (pinfunction "2_2") (pintype "passive"))
      (node (ref "C6") (pin "2") (pinfunction "2_2") (pintype "passive"))
      (node (ref "C7") (pin "2") (pinfunction "2_2") (pintype "passive"))
      (node (ref "C8") (pin "2") (pinfunction "2_2") (pintype "passive"))
      (node (ref "C9") (pin "2") (pinfunction "2_2") (pintype "passive"))
      (node (ref "C_IN") (pin "2") (pinfunction "2_2") (pintype "passive"))
      (node (ref "C_OUT") (pin "2") (pinfunction "2_2") (pintype "passive"))
      (node (ref "C_VC") (pin "2") (pinfunction "2_2") (pintype "passive"))
      (node (ref "DEBUG") (pin "3") (pinfunction "3_3") (pintype "passive"))
      (node (ref "DEBUG") (pin "4") (pinfunction "4_4") (pintype "passive"))
      (node (ref "FP2") (pin "1") (pinfunction "1_1") (pintype "passive"))
      (node (ref "HC-05") (pin "4") (pinfunction "GND_4") (pintype "power_in"))
      (node (ref "IC3") (pin "4") (pinfunction "SGND_4") (pintype "power_in"))
      (node (ref "IC3") (pin "6") (pinfunction "PGND_6") (pintype "power_in"))
      (node (ref "IC3") (pin "9") (pinfunction "EP_9") (pintype "power_in"))
      (node (ref "MOTOR_LEFT") (pin "3") (pinfunction "3_3") (pintype "bidirectional"))
      (node (ref "MOTOR_RIGHT") (pin "3") (pinfunction "3_3") (pintype "bidirectional"))
      (node (ref "OLED") (pin "1") (pinfunction "GND_1") (pintype "power_in"))
      (node (ref "Q1") (pin "2") (pinfunction "S_2") (pintype "passive"))
      (node (ref "Q2") (pin "2") (pinfunction "S_2") (pintype "passive"))
      (node (ref "Q3") (pin "2") (pinfunction "S_2") (pintype "passive"))
      (node (ref "Q4") (pin "2") (pinfunction "S_2") (pintype "passive"))
      (node (ref "Q5") (pin "2") (pinfunction "S_2") (pintype "passive"))
      (node (ref "R10") (pin "1") (pinfunction "1_1") (pintype "passive"))
      (node (ref "R11") (pin "1") (pinfunction "1_1") (pintype "passive"))
      (node (ref "R14") (pin "1") (pinfunction "1_1") (pintype "passive"))
      (node (ref "R15") (pin "1") (pinfunction "1_1") (pintype "passive"))
      (node (ref "R25") (pin "1") (pinfunction "1_1") (pintype "passive"))
      (node (ref "R27") (pin "1") (pinfunction "1_1") (pintype "passive"))
      (node (ref "R3") (pin "1") (pinfunction "1_1") (pintype "passive"))
      (node (ref "R31") (pin "1") (pinfunction "1_1") (pintype "passive"))
      (node (ref "R4") (pin "1") (pinfunction "1_1") (pintype "passive"))
      (node (ref "R5") (pin "1") (pinfunction "1_1") (pintype "passive"))
      (node (ref "R8") (pin "1") (pinfunction "1_1") (pintype "passive"))
      (node (ref "RB") (pin "1") (pinfunction "1_1") (pintype "passive"))
      (node (ref "R_FBB") (pin "1") (pinfunction "1_1") (pintype "passive"))
      (node (ref "S1") (pin "10") (pinfunction "GND_10") (pintype "power_in"))
      (node (ref "S1") (pin "5") (pinfunction "GND_5") (pintype "power_in"))
      (node (ref "S1") (pin "9") (pinfunction "GND_9") (pintype "power_in"))
      (node (ref "U$10") (pin "1") (pinfunction "1_1") (pintype "bidirectional"))
      (node (ref "U$6") (pin "2") (pinfunction "2_2") (pintype "bidirectional"))
      (node (ref "U$7") (pin "2") (pinfunction "2_2") (pintype "bidirectional"))
      (node (ref "U3") (pin "18") (pinfunction "VSS_4_18") (pintype "power_in"))
      (node (ref "U3") (pin "63") (pinfunction "VSS_3_63") (pintype "power_in"))
      (node (ref "VR1") (pin "1") (pinfunction "GND_1") (pintype "power_in"))
    )
    (net (code "46") (name "GND_A") (class "Default")
      (node (ref "C28") (pin "2") (pinfunction "2_2") (pintype "passive"))
      (node (ref "C29") (pin "2") (pinfunction "2_2") (pintype "passive"))
      (node (ref "C34") (pin "2") (pinfunction "2_2") (pintype "passive"))
      (node (ref "C35") (pin "2") (pinfunction "2_2") (pintype "passive"))
      (node (ref "C43") (pin "2") (pinfunction "2_2") (pintype "passive"))
      (node (ref "C44") (pin "2") (pinfunction "2_2") (pintype "passive"))
      (node (ref "FP2") (pin "2") (pinfunction "2_2") (pintype "passive"))
      (node (ref "R1") (pin "1") (pinfunction "1_1") (pintype "passive"))
      (node (ref "R13") (pin "1") (pinfunction "1_1") (pintype "passive"))
      (node (ref "R16") (pin "1") (pinfunction "1_1") (pintype "passive"))
      (node (ref "R2") (pin "1") (pinfunction "1_1") (pintype "passive"))
      (node (ref "U3") (pin "12") (pinfunction "VSSA_12") (pintype "power_in"))
      (node (ref "U4") (pin "4") (pinfunction "GNDA_4") (pintype "power_in"))
      (node (ref "U4") (pin "6") (pinfunction "GNDIO_6") (pintype "power_in"))
      (node (ref "U4") (pin "7") (pinfunction "PS_7") (pintype "input"))
    )
    (net (code "47") (name "GND_M") (class "Default")
      (node (ref "C1") (pin "2") (pinfunction "2_2") (pintype "passive"))
      (node (ref "C2") (pin "2") (pinfunction "2_2") (pintype "passive"))
      (node (ref "C3") (pin "2") (pinfunction "-_2") (pintype "passive"))
      (node (ref "U$6") (pin "1") (pinfunction "1_1") (pintype "bidirectional"))
      (node (ref "U1") (pin "10") (pinfunction "M_GND2_10") (pintype "power_in"))
      (node (ref "U1") (pin "18") (pinfunction "GND_18") (pintype "power_in"))
      (node (ref "U1") (pin "3") (pinfunction "M_GND1_3") (pintype "power_in"))
      (node (ref "U1") (pin "4") (pinfunction "M_GND1_4") (pintype "power_in"))
      (node (ref "U1") (pin "9") (pinfunction "M_GND2_9") (pintype "power_in"))
    )
    (net (code "48") (name "GND_SW") (class "Default")
      (node (ref "C15") (pin "2") (pinfunction "2_2") (pintype "passive"))
      (node (ref "C16") (pin "2") (pinfunction "2_2") (pintype "passive"))
      (node (ref "C17") (pin "2") (pinfunction "2_2") (pintype "passive"))
      (node (ref "C18") (pin "2") (pinfunction "2_2") (pintype "passive"))
      (node (ref "C19") (pin "2") (pinfunction "2_2") (pintype "passive"))
      (node (ref "C20") (pin "2") (pinfunction "2_2") (pintype "passive"))
      (node (ref "C21") (pin "2") (pinfunction "2_2") (pintype "passive"))
      (node (ref "C22") (pin "2") (pinfunction "2_2") (pintype "passive"))
      (node (ref "C23") (pin "2") (pinfunction "2_2") (pintype "passive"))
      (node (ref "C24") (pin "2") (pinfunction "2_2") (pintype "passive"))
      (node (ref "C25") (pin "2") (pinfunction "2_2") (pintype "passive"))
      (node (ref "IC2") (pin "11") (pinfunction "NC_11") (pintype "bidirectional"))
      (node (ref "IC2") (pin "12") (pinfunction "NC_12") (pintype "bidirectional"))
      (node (ref "IC2") (pin "13") (pinfunction "MODE_13") (pintype "bidirectional"))
      (node (ref "IC2") (pin "20") (pinfunction "AGND_20") (pintype "bidirectional"))
      (node (ref "IC2") (pin "21") (pinfunction "PGND_21") (pintype "bidirectional"))
      (node (ref "R19") (pin "2") (pinfunction "2_2") (pintype "passive"))
      (node (ref "R21") (pin "2") (pinfunction "2_2") (pintype "passive"))
      (node (ref "R24") (pin "1") (pinfunction "1_1") (pintype "passive"))
      (node (ref "U$7") (pin "1") (pinfunction "1_1") (pintype "bidirectional"))
    )
    (net (code "49") (name "LED_B") (class "Default")
      (node (ref "LED_B") (pin "A") (pinfunction "A_A") (pintype "passive"))
      (node (ref "U3") (pin "50") (pinfunction "PA15_50") (pintype "bidirectional"))
    )
    (net (code "50") (name "LED_G") (class "Default")
      (node (ref "LED_G") (pin "A") (pinfunction "A_A") (pintype "passive"))
      (node (ref "U3") (pin "51") (pinfunction "PC10_51") (pintype "bidirectional"))
    )
    (net (code "51") (name "LED_R") (class "Default")
      (node (ref "LED_R") (pin "A") (pinfunction "A_A") (pintype "passive"))
      (node (ref "U3") (pin "52") (pinfunction "PC11_52") (pintype "bidirectional"))
    )
    (net (code "52") (name "L_EMITTER") (class "Default")
      (node (ref "Q4") (pin "1") (pinfunction "G_1") (pintype "passive"))
      (node (ref "R11") (pin "2") (pinfunction "2_2") (pintype "passive"))
      (node (ref "U3") (pin "22") (pinfunction "PA6_22") (pintype "bidirectional"))
    )
    (net (code "53") (name "L_RECEIVER") (class "Default")
      (node (ref "D4") (pin "E") (pinfunction "E_-_E") (pintype "output"))
      (node (ref "R13") (pin "2") (pinfunction "2_2") (pintype "passive"))
      (node (ref "U3") (pin "8") (pinfunction "PC0_8") (pintype "bidirectional"))
    )
    (net (code "54") (name "Net-(5V_PWR-K)") (class "Default")
      (node (ref "5V_PWR") (pin "C") (pinfunction "K_C") (pintype "passive"))
      (node (ref "R25") (pin "2") (pinfunction "2_2") (pintype "passive"))
    )
    (net (code "55") (name "Net-(BOOT-Pad3)") (class "Default")
      (node (ref "BOOT") (pin "3") (pinfunction "3_3") (pintype "passive"))
      (node (ref "R34") (pin "1") (pinfunction "1_1") (pintype "passive"))
    )
    (net (code "56") (name "Net-(BOOT-Pad4)") (class "Default")
      (node (ref "BOOT") (pin "4") (pinfunction "4_4") (pintype "passive"))
      (node (ref "R33") (pin "2") (pinfunction "2_2") (pintype "passive"))
    )
    (net (code "57") (name "Net-(BTN_SEL-Pad1)") (class "Default")
      (node (ref "BTN_SEL") (pin "1") (pinfunction "1_1") (pintype "bidirectional"))
      (node (ref "BTN_SEL") (pin "2") (pinfunction "2_2") (pintype "bidirectional"))
      (node (ref "R29") (pin "2") (pinfunction "2_2") (pintype "passive"))
      (node (ref "R30") (pin "1") (pinfunction "1_1") (pintype "passive"))
    )
    (net (code "58") (name "Net-(C14-Pad1)") (class "Default")
      (node (ref "C14") (pin "1") (pinfunction "1_1") (pintype "passive"))
      (node (ref "IC2") (pin "4") (pinfunction "SW_4") (pintype "bidirectional"))
      (node (ref "IC2") (pin "5") (pinfunction "SW_5") (pintype "bidirectional"))
      (node (ref "IC2") (pin "6") (pinfunction "SW_6") (pintype "bidirectional"))
      (node (ref "IC2") (pin "7") (pinfunction "SW_7") (pintype "bidirectional"))
      (node (ref "L1") (pin "2") (pinfunction "2_2") (pintype "bidirectional"))
      (node (ref "R17") (pin "1") (pinfunction "1_1") (pintype "passive"))
    )
    (net (code "59") (name "Net-(C23-Pad1)") (class "Default")
      (node (ref "C23") (pin "1") (pinfunction "1_1") (pintype "passive"))
      (node (ref "R20") (pin "2") (pinfunction "2_2") (pintype "passive"))
    )
    (net (code "60") (name "Net-(FL_EMITTER--_CATHODE)") (class "Default")
      (node (ref "FL_EMITTER") (pin "-") (pinfunction "-_CATHODE_-") (pintype "passive"))
      (node (ref "R6") (pin "2") (pinfunction "2_2") (pintype "passive"))
    )
    (net (code "61") (name "Net-(FR_EMITTER--_CATHODE)") (class "Default")
      (node (ref "FR_EMITTER") (pin "-") (pinfunction "-_CATHODE_-") (pintype "passive"))
      (node (ref "R9") (pin "2") (pinfunction "2_2") (pintype "passive"))
    )
    (net (code "62") (name "Net-(IC2-BOOT)") (class "Default")
      (node (ref "C14") (pin "2") (pinfunction "2_2") (pintype "passive"))
      (node (ref "IC2") (pin "8") (pinfunction "BOOT_8") (pintype "bidirectional"))
    )
    (net (code "63") (name "Net-(IC2-COMP)") (class "Default")
      (node (ref "C21") (pin "1") (pinfunction "1_1") (pintype "passive"))
      (node (ref "IC2") (pin "18") (pinfunction "COMP_18") (pintype "bidirectional"))
      (node (ref "R20") (pin "1") (pinfunction "1_1") (pintype "passive"))
    )
    (net (code "64") (name "Net-(IC2-EN)") (class "Default")
      (node (ref "C15") (pin "1") (pinfunction "1_1") (pintype "passive"))
      (node (ref "IC2") (pin "1") (pinfunction "VCC_1") (pintype "bidirectional"))
      (node (ref "IC2") (pin "2") (pinfunction "EN_2") (pintype "bidirectional"))
    )
    (net (code "65") (name "Net-(IC2-FB)") (class "Default")
      (node (ref "IC2") (pin "17") (pinfunction "FB_17") (pintype "bidirectional"))
      (node (ref "R18") (pin "2") (pinfunction "2_2") (pintype "passive"))
      (node (ref "R19") (pin "1") (pinfunction "1_1") (pintype "passive"))
    )
    (net (code "66") (name "Net-(IC2-FSW)") (class "Default")
      (node (ref "IC2") (pin "3") (pinfunction "FSW_3") (pintype "bidirectional"))
      (node (ref "R17") (pin "2") (pinfunction "2_2") (pintype "passive"))
    )
    (net (code "67") (name "Net-(IC2-ILIM)") (class "Default")
      (node (ref "IC2") (pin "19") (pinfunction "ILIM_19") (pintype "bidirectional"))
      (node (ref "R21") (pin "1") (pinfunction "1_1") (pintype "passive"))
    )
    (net (code "68") (name "Net-(IC2-SS)") (class "Default")
      (node (ref "C18") (pin "1") (pinfunction "1_1") (pintype "passive"))
      (node (ref "IC2") (pin "10") (pinfunction "SS_10") (pintype "bidirectional"))
    )
    (net (code "69") (name "Net-(IC3-VCON)") (class "Default")
      (node (ref "C_VC") (pin "1") (pinfunction "1_1") (pintype "passive"))
      (node (ref "IC3") (pin "2") (pinfunction "VCON_2") (pintype "bidirectional"))
      (node (ref "RB") (pin "2") (pinfunction "2_2") (pintype "passive"))
      (node (ref "RT") (pin "1") (pinfunction "1_1") (pintype "passive"))
    )
    (net (code "70") (name "Net-(IC3-VREF)") (class "Default")
      (node (ref "IC3") (pin "8") (pinfunction "VREF_8") (pintype "input"))
      (node (ref "RT") (pin "2") (pinfunction "2_2") (pintype "passive"))
    )
    (net (code "71") (name "Net-(LED_B-K)") (class "Default")
      (node (ref "LED_B") (pin "C") (pinfunction "K_C") (pintype "passive"))
      (node (ref "R5") (pin "2") (pinfunction "2_2") (pintype "passive"))
    )
    (net (code "72") (name "Net-(LED_G-K)") (class "Default")
      (node (ref "LED_G") (pin "C") (pinfunction "K_C") (pintype "passive"))
      (node (ref "R4") (pin "2") (pinfunction "2_2") (pintype "passive"))
    )
    (net (code "73") (name "Net-(LED_R-K)") (class "Default")
      (node (ref "LED_R") (pin "C") (pinfunction "K_C") (pintype "passive"))
      (node (ref "R14") (pin "2") (pinfunction "2_2") (pintype "passive"))
    )
    (net (code "74") (name "Net-(L_EMITTER--_CATHODE)") (class "Default")
      (node (ref "L_EMITTER") (pin "-") (pinfunction "-_CATHODE_-") (pintype "passive"))
      (node (ref "R7") (pin "2") (pinfunction "2_2") (pintype "passive"))
    )
    (net (code "75") (name "Net-(Q1-D)") (class "Default")
      (node (ref "Q1") (pin "3") (pinfunction "D_3") (pintype "passive"))
      (node (ref "R6") (pin "1") (pinfunction "1_1") (pintype "passive"))
    )
    (net (code "76") (name "Net-(Q2-D)") (class "Default")
      (node (ref "Q2") (pin "3") (pinfunction "D_3") (pintype "passive"))
      (node (ref "R9") (pin "1") (pinfunction "1_1") (pintype "passive"))
    )
    (net (code "77") (name "Net-(Q3-D)") (class "Default")
      (node (ref "Q3") (pin "3") (pinfunction "D_3") (pintype "passive"))
      (node (ref "U$1") (pin "-") (pinfunction "-_CATHODE_-") (pintype "passive"))
      (node (ref "U$4") (pin "-") (pinfunction "-_-") (pintype "bidirectional"))
    )
    (net (code "78") (name "Net-(Q4-D)") (class "Default")
      (node (ref "Q4") (pin "3") (pinfunction "D_3") (pintype "passive"))
      (node (ref "R7") (pin "1") (pinfunction "1_1") (pintype "passive"))
    )
    (net (code "79") (name "Net-(Q5-D)") (class "Default")
      (node (ref "Q5") (pin "3") (pinfunction "D_3") (pintype "passive"))
      (node (ref "R12") (pin "1") (pinfunction "1_1") (pintype "passive"))
    )
    (net (code "80") (name "Net-(R26-Pad2)") (class "Default")
      (node (ref "R26") (pin "2") (pinfunction "2_2") (pintype "passive"))
      (node (ref "U$10") (pin "2") (pinfunction "2_2") (pintype "bidirectional"))
    )
    (net (code "81") (name "Net-(R_EMITTER--_CATHODE)") (class "Default")
      (node (ref "R12") (pin "2") (pinfunction "2_2") (pintype "passive"))
      (node (ref "R_EMITTER") (pin "-") (pinfunction "-_CATHODE_-") (pintype "passive"))
    )
    (net (code "82") (name "Net-(S1-FB)") (class "Default")
      (node (ref "R_FBB") (pin "2") (pinfunction "2_2") (pintype "passive"))
      (node (ref "R_FBT") (pin "2") (pinfunction "2_2") (pintype "passive"))
      (node (ref "S1") (pin "2") (pinfunction "FB_2") (pintype "bidirectional"))
    )
    (net (code "83") (name "Net-(S1-PG)") (class "Default")
      (node (ref "R23") (pin "1") (pinfunction "1_1") (pintype "passive"))
      (node (ref "S1") (pin "3") (pinfunction "PG_3") (pintype "bidirectional"))
    )
    (net (code "84") (name "Net-(S1-SS)") (class "Default")
      (node (ref "C31") (pin "1") (pinfunction "1_1") (pintype "passive"))
      (node (ref "S1") (pin "1") (pinfunction "SS_1") (pintype "bidirectional"))
    )
    (net (code "85") (name "Net-(SW-COM)") (class "Default")
      (node (ref "R28") (pin "2") (pinfunction "2_2") (pintype "passive"))
      (node (ref "SW") (pin "1") (pinfunction "1_1") (pintype "bidirectional"))
      (node (ref "SW") (pin "2_COM") (pinfunction "COM_2_COM") (pintype "bidirectional"))
      (node (ref "U$10") (pin "3") (pinfunction "3_3") (pintype "bidirectional"))
    )
    (net (code "86") (name "Net-(U3-VCAP_1)") (class "Default")
      (node (ref "C45") (pin "1") (pinfunction "1_1") (pintype "passive"))
      (node (ref "U3") (pin "31") (pinfunction "VCAP_1_31") (pintype "power_in"))
    )
    (net (code "87") (name "Net-(U3-VCAP_2)") (class "Default")
      (node (ref "C46") (pin "1") (pinfunction "1_1") (pintype "passive"))
      (node (ref "U3") (pin "47") (pinfunction "VCAP_2_47") (pintype "power_in"))
    )
    (net (code "88") (name "RESET") (class "Default")
      (node (ref "BTN_RST") (pin "3") (pinfunction "3_3") (pintype "bidirectional"))
      (node (ref "BTN_RST") (pin "4") (pinfunction "4_4") (pintype "bidirectional"))
      (node (ref "C36") (pin "1") (pinfunction "1_1") (pintype "passive"))
      (node (ref "U3") (pin "7") (pinfunction "NRST_7") (pintype "bidirectional"))
    )
    (net (code "89") (name "R_EMITTER") (class "Default")
      (node (ref "Q5") (pin "1") (pinfunction "G_1") (pintype "passive"))
      (node (ref "R15") (pin "2") (pinfunction "2_2") (pintype "passive"))
      (node (ref "U3") (pin "27") (pinfunction "PB1_27") (pintype "bidirectional"))
    )
    (net (code "90") (name "R_RECEIVER") (class "Default")
      (node (ref "D6") (pin "E") (pinfunction "E_-_E") (pintype "output"))
      (node (ref "R2") (pin "2") (pinfunction "2_2") (pintype "passive"))
      (node (ref "U3") (pin "11") (pinfunction "PC3_11") (pintype "bidirectional"))
    )
    (net (code "91") (name "VOLTM_BATT") (class "Default")
      (node (ref "R28") (pin "1") (pinfunction "1_1") (pintype "passive"))
      (node (ref "R31") (pin "2") (pinfunction "2_2") (pintype "passive"))
      (node (ref "U3") (pin "17") (pinfunction "PA3_17") (pintype "bidirectional"))
    )
    (net (code "92") (name "VOLTM_BOOST") (class "Default")
      (node (ref "R22") (pin "1") (pinfunction "1_1") (pintype "passive"))
      (node (ref "R24") (pin "2") (pinfunction "2_2") (pintype "passive"))
      (node (ref "U3") (pin "16") (pinfunction "PA2_16") (pintype "bidirectional"))
    )
    (net (code "93") (name "VOLTM_CELL1") (class "Default")
      (node (ref "R26") (pin "1") (pinfunction "1_1") (pintype "passive"))
      (node (ref "R27") (pin "2") (pinfunction "2_2") (pintype "passive"))
      (node (ref "U3") (pin "20") (pinfunction "PA4_20") (pintype "bidirectional"))
    )
    (net (code "94") (name "V_BAT") (class "Default")
      (node (ref "C16") (pin "1") (pinfunction "1_1") (pintype "passive"))
      (node (ref "C17") (pin "1") (pinfunction "1_1") (pintype "passive"))
      (node (ref "C25") (pin "1") (pinfunction "1_1") (pintype "passive"))
      (node (ref "C32") (pin "1") (pinfunction "1_1") (pintype "passive"))
      (node (ref "IC2") (pin "9") (pinfunction "VIN_9") (pintype "bidirectional"))
      (node (ref "L1") (pin "1") (pinfunction "1_1") (pintype "bidirectional"))
      (node (ref "S1") (pin "7") (pinfunction "EN_7") (pintype "bidirectional"))
      (node (ref "S1") (pin "8") (pinfunction "VIN_8") (pintype "power_in"))
      (node (ref "SW") (pin "3") (pinfunction "3_3") (pintype "bidirectional"))
    )
    (net (code "95") (name "unconnected-(HC-05-EN-Pad6)") (class "Default")
      (node (ref "HC-05") (pin "6") (pinfunction "EN_6") (pintype "bidirectional"))
    )
    (net (code "96") (name "unconnected-(HC-05-STATE-Pad1)") (class "Default")
      (node (ref "HC-05") (pin "1") (pinfunction "STATE_1") (pintype "bidirectional"))
    )
    (net (code "97") (name "unconnected-(IC3-EN-Pad1)") (class "Default")
      (node (ref "IC3") (pin "1") (pinfunction "EN_1") (pintype "bidirectional"))
    )
    (net (code "98") (name "unconnected-(U3-PA12-Pad45)") (class "Default")
      (node (ref "U3") (pin "45") (pinfunction "PA12_45") (pintype "bidirectional"))
    )
    (net (code "99") (name "unconnected-(U3-PB11-Pad30)") (class "Default")
      (node (ref "U3") (pin "30") (pinfunction "PB11_30") (pintype "bidirectional"))
    )
    (net (code "100") (name "unconnected-(U3-PC6-Pad37)") (class "Default")
      (node (ref "U3") (pin "37") (pinfunction "PC6_37") (pintype "bidirectional"))
    )
    (net (code "101") (name "unconnected-(U3-PC7-Pad38)") (class "Default")
      (node (ref "U3") (pin "38") (pinfunction "PC7_38") (pintype "bidirectional"))
    )
    (net (code "102") (name "unconnected-(U3-PC8-Pad39)") (class "Default")
      (node (ref "U3") (pin "39") (pinfunction "PC8_39") (pintype "bidirectional"))
    )
    (net (code "103") (name "unconnected-(U3-PC12-Pad53)") (class "Default")
      (node (ref "U3") (pin "53") (pinfunction "PC12_53") (pintype "bidirectional"))
    )
    (net (code "104") (name "unconnected-(U3-PC13-TAMPER-RTC-Pad2)") (class "Default")
      (node (ref "U3") (pin "2") (pinfunction "PC13-TAMPER-RTC_2") (pintype "bidirectional"))
    )
    (net (code "105") (name "unconnected-(U3-PC14-OSC32_IN-Pad3)") (class "Default")
      (node (ref "U3") (pin "3") (pinfunction "PC14-OSC32_IN_3") (pintype "bidirectional"))
    )
    (net (code "106") (name "unconnected-(U3-PC15-OSC32_OUT-Pad4)") (class "Default")
      (node (ref "U3") (pin "4") (pinfunction "PC15-OSC32_OUT_4") (pintype "bidirectional"))
    )
    (net (code "107") (name "unconnected-(U3-PH0_OSC_IN-Pad5)") (class "Default")
      (node (ref "U3") (pin "5") (pinfunction "PH0_OSC_IN_5") (pintype "input"))
    )
    (net (code "108") (name "unconnected-(U3-PH1_OSC_OUT-Pad6)") (class "Default")
      (node (ref "U3") (pin "6") (pinfunction "PH1_OSC_OUT_6") (pintype "output"))
    )
    (net (code "109") (name "unconnected-(U4-INT2-Pad1)") (class "Default")
      (node (ref "U4") (pin "1") (pinfunction "INT2_1") (pintype "bidirectional"))
    )
    (net (code "110") (name "unconnected-(U4-INT4-Pad13)") (class "Default")
      (node (ref "U4") (pin "13") (pinfunction "INT4_13") (pintype "bidirectional"))
    )
  )
)
